# SCH_WGE_Slimevr_rev_2_2_2023-11-07.net
KiCad netlist of a schematic drawn in EasyEDA
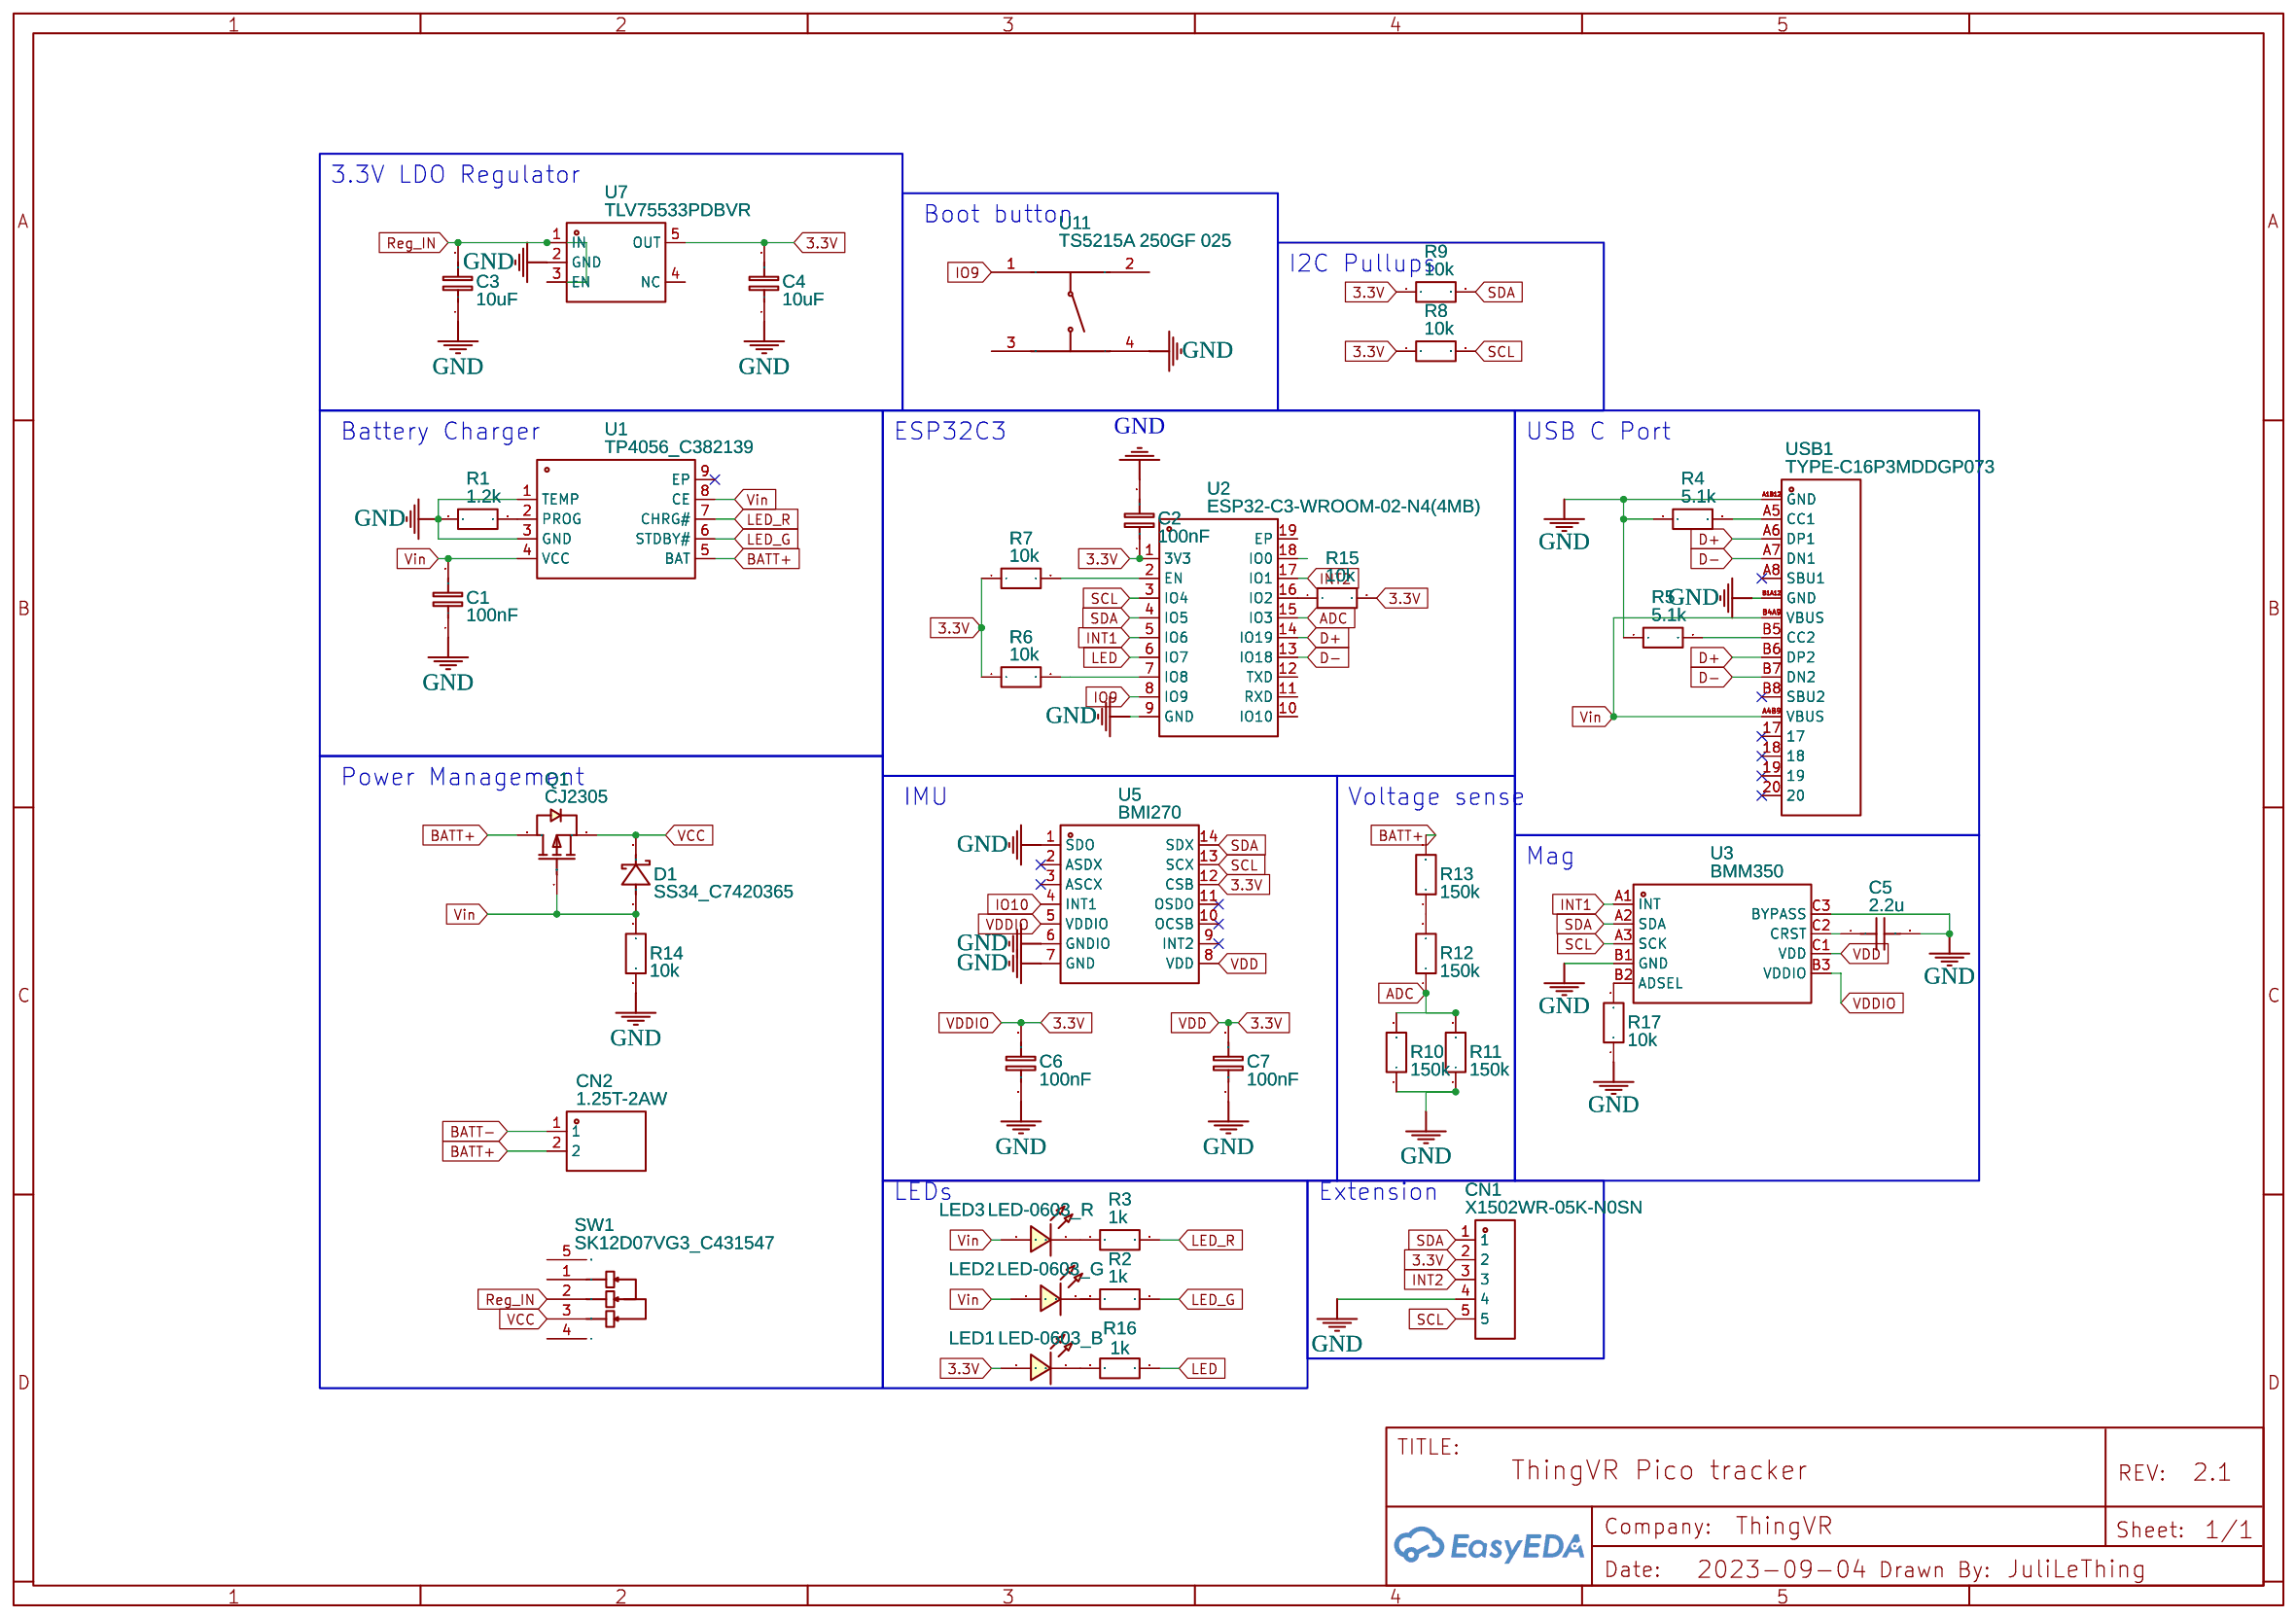
[diagram p0: schematic sheet]

(export (version "E")
  (design (tool "Eeschema 10.0.6"))
  (components
    (comp (ref "C1")
      (value "100nF")
      (fields (field (name "Manufacturer Part") "0603F104Z500CT") (field (name "Manufacturer") "Walsin(华新科)"))
      (libsource (lib "") (part "C_1206_EU"))
    )
    (comp (ref "C2")
      (value "100nF")
      (fields
        (field (name "Manufacturer Part") "CC0805ZRY5V8BB104")
        (field (name "Manufacturer") "YAGEO(国巨)")
      )
      (libsource (lib "") (part "C_0805_EU"))
    )
    (comp (ref "C3")
      (value "10uF")
      (fields
        (field (name "Manufacturer Part") "CC0805KKX5R9BB105")
        (field (name "Manufacturer") "YAGEO(国巨)")
      )
      (libsource (lib "") (part "C_0805_EU_1"))
    )
    (comp (ref "C4")
      (value "10uF")
      (fields
        (field (name "Manufacturer Part") "CC0805KKX5R9BB105")
        (field (name "Manufacturer") "YAGEO(国巨)")
      )
      (libsource (lib "") (part "C_0805_EU_1"))
    )
    (comp (ref "C5") (value "2.2u") (libsource (lib "") (part "C_0603_US")))
    (comp (ref "C6")
      (value "100nF")
      (fields
        (field (name "Manufacturer Part") "CC0805ZRY5V8BB104")
        (field (name "Manufacturer") "YAGEO(国巨)")
      )
      (libsource (lib "") (part "C_0805_EU_2"))
    )
    (comp (ref "C7")
      (value "100nF")
      (fields
        (field (name "Manufacturer Part") "CC0805ZRY5V8BB104")
        (field (name "Manufacturer") "YAGEO(国巨)")
      )
      (libsource (lib "") (part "C_0805_EU_2"))
    )
    (comp (ref "CN1")
      (value "X1502WR-05K-N0SN")
      (fields (field (name "Manufacturer") "XKB Connectivity(中国星坤)"))
      (libsource (lib "") (part "X1502WR-05K-N0SN"))
    )
    (comp (ref "CN2")
      (value "1.25T-2AW")
      (fields (field (name "Manufacturer") "BOOMELE"))
      (libsource (lib "") (part "1.25T-2AW"))
    )
    (comp (ref "D1")
      (value "SS34_C7420365")
      (fields (field (name "Manufacturer Part") "SS34") (field (name "Manufacturer") "宏迦橙"))
      (libsource (lib "") (part "SS34_C7420365"))
    )
    (comp (ref "LED1")
      (value "LED-0603_B")
      (fields
        (field (name "Manufacturer Part") "19-217/BHC-ZL1M2RY/3T")
        (field (name "Manufacturer") "EVERLIGHT(台湾亿光)")
      )
      (libsource (lib "") (part "LED-0603_B"))
    )
    (comp (ref "LED2")
      (value "LED-0603_G")
      (fields (field (name "Manufacturer Part") "NCD0805G1") (field (name "Manufacturer") "国星光电"))
      (libsource (lib "") (part "LED-0805_G"))
    )
    (comp (ref "LED3")
      (value "LED-0603_R")
      (fields
        (field (name "Manufacturer Part") "17-21SURC/S530-A3/TR8")
        (field (name "Manufacturer") "EVERLIGHT(台湾亿光)")
      )
      (libsource (lib "") (part "LED-0805_R"))
    )
    (comp (ref "Q1")
      (value "CJ2305")
      (fields (field (name "Manufacturer") "CJ(江苏长电/长晶)"))
      (libsource (lib "") (part "CJ2305"))
    )
    (comp (ref "R1")
      (value "1.2k")
      (fields (field (name "Manufacturer Part") "RMC08051.2K1%N") (field (name "Manufacturer") "Tyohm(幸亚电阻)"))
      (libsource (lib "") (part "R_1206_EU"))
    )
    (comp (ref "R2")
      (value "1k")
      (fields
        (field (name "Manufacturer Part") "QR0805F1K00P05Z")
        (field (name "Manufacturer") "EVER OHMS(天二科技)")
      )
      (libsource (lib "") (part "R_0805_EU_2"))
    )
    (comp (ref "R3")
      (value "1k")
      (fields
        (field (name "Manufacturer Part") "QR0805F1K00P05Z")
        (field (name "Manufacturer") "EVER OHMS(天二科技)")
      )
      (libsource (lib "") (part "R_0805_EU_1"))
    )
    (comp (ref "R4")
      (value "5.1k")
      (fields (field (name "Manufacturer Part") "RMC08055.1K5%N") (field (name "Manufacturer") "Tyohm(幸亚电阻)"))
      (libsource (lib "") (part "R_0805_EU_1"))
    )
    (comp (ref "R5")
      (value "5.1k")
      (fields (field (name "Manufacturer Part") "RMC08055.1K5%N") (field (name "Manufacturer") "Tyohm(幸亚电阻)"))
      (libsource (lib "") (part "R_0805_EU_1"))
    )
    (comp (ref "R6")
      (value "10k")
      (fields (field (name "Manufacturer Part") "AC0805JR-0710KL") (field (name "Manufacturer") "YAGEO(国巨)"))
      (libsource (lib "") (part "R_0805_EU_1"))
    )
    (comp (ref "R7")
      (value "10k")
      (fields (field (name "Manufacturer Part") "AC0805JR-0710KL") (field (name "Manufacturer") "YAGEO(国巨)"))
      (libsource (lib "") (part "R_0805_EU_1"))
    )
    (comp (ref "R8")
      (value "10k")
      (fields (field (name "Manufacturer Part") "AC0805JR-0710KL") (field (name "Manufacturer") "YAGEO(国巨)"))
      (libsource (lib "") (part "R_0805_EU_1"))
    )
    (comp (ref "R9")
      (value "10k")
      (fields (field (name "Manufacturer Part") "AC0805JR-0710KL") (field (name "Manufacturer") "YAGEO(国巨)"))
      (libsource (lib "") (part "R_0805_EU_1"))
    )
    (comp (ref "R10")
      (value "150k")
      (fields (field (name "Manufacturer Part") "RC0805JR-07300KL") (field (name "Manufacturer") "YAGEO(国巨)"))
      (libsource (lib "") (part "R_0805_EU"))
    )
    (comp (ref "R11")
      (value "150k")
      (fields (field (name "Manufacturer Part") "RC0805JR-07300KL") (field (name "Manufacturer") "YAGEO(国巨)"))
      (libsource (lib "") (part "R_0805_EU"))
    )
    (comp (ref "R12")
      (value "150k")
      (fields (field (name "Manufacturer Part") "RC0805JR-07300KL") (field (name "Manufacturer") "YAGEO(国巨)"))
      (libsource (lib "") (part "R_0805_EU"))
    )
    (comp (ref "R13")
      (value "150k")
      (fields (field (name "Manufacturer Part") "RC0805JR-07300KL") (field (name "Manufacturer") "YAGEO(国巨)"))
      (libsource (lib "") (part "R_0805_EU"))
    )
    (comp (ref "R14")
      (value "10k")
      (fields (field (name "Manufacturer Part") "AC0805JR-0710KL") (field (name "Manufacturer") "YAGEO(国巨)"))
      (libsource (lib "") (part "R_0805_EU"))
    )
    (comp (ref "R15")
      (value "10k")
      (fields (field (name "Manufacturer Part") "AC0805JR-0710KL") (field (name "Manufacturer") "YAGEO(国巨)"))
      (libsource (lib "") (part "R_0805_EU_1"))
    )
    (comp (ref "R16")
      (value "1k")
      (fields (field (name "Manufacturer Part") "SCR0603J1K") (field (name "Manufacturer") "VO(翔胜)"))
      (libsource (lib "") (part "R_0603_EU"))
    )
    (comp (ref "R17") (value "10k") (libsource (lib "") (part "R_0805_EU")))
    (comp (ref "SW1")
      (value "SK12D07VG3_C431547")
      (fields (field (name "Manufacturer Part") "SK12D07VG3") (field (name "Manufacturer") "SHOU HAN"))
      (libsource (lib "") (part "SK12D07VG3_C431547"))
    )
    (comp (ref "U1")
      (value "TP4056_C382139")
      (fields (field (name "Manufacturer Part") "TP4056") (field (name "Manufacturer") "TPOWER(天源)"))
      (libsource (lib "") (part "TP4056_C382139"))
    )
    (comp (ref "U2")
      (value "ESP32-C3-WROOM-02-N4(4MB)")
      (fields
        (field (name "Manufacturer Part") "ESP32-C3-WROOM-02-N4")
        (field (name "Manufacturer") "ESPRESSIF(乐鑫)")
      )
      (libsource (lib "") (part "ESP32-C3-WROOM-02-N4(4MB)"))
    )
    (comp (ref "U3")
      (value "BMM350")
      (fields (field (name "Manufacturer") "Bosch(博世)"))
      (libsource (lib "") (part "BMM350"))
    )
    (comp (ref "U5")
      (value "BMI270")
      (fields (field (name "Manufacturer") "Bosch(博世)"))
      (libsource (lib "") (part "BMI270"))
    )
    (comp (ref "U7")
      (value "TLV75533PDBVR")
      (fields (field (name "Manufacturer") "TI(德州仪器)"))
      (libsource (lib "") (part "TLV75533PDBVR"))
    )
    (comp (ref "U11")
      (value "TS5215A 250GF 025")
      (fields
        (field (name "Manufacturer Part") "TS5215A 250gf 025")
        (field (name "Manufacturer") "SHOU HAN(首韩)")
      )
      (libsource (lib "") (part "TS5215A 250GF 025"))
    )
    (comp (ref "USB1")
      (value "TYPE-C16P3MDDGP073")
      (fields (field (name "Manufacturer") "SHOU HAN(首韩)"))
      (libsource (lib "") (part "TYPE-C16P3MDDGP073"))
    )
  )
  (nets
    (net (code "1") (name "3.3V") (class "Default")
      (node (ref "C2") (pin "1") (pinfunction "1_1") (pintype "unspecified"))
      (node (ref "C4") (pin "2") (pinfunction "2_2") (pintype "unspecified"))
      (node (ref "C6") (pin "2") (pinfunction "2_2") (pintype "unspecified"))
      (node (ref "C7") (pin "2") (pinfunction "2_2") (pintype "unspecified"))
      (node (ref "CN1") (pin "2") (pinfunction "2_2") (pintype "unspecified"))
      (node (ref "LED1") (pin "1") (pinfunction "1_1") (pintype "unspecified"))
      (node (ref "R15") (pin "2") (pinfunction "2_2") (pintype "unspecified"))
      (node (ref "R6") (pin "1") (pinfunction "1_1") (pintype "unspecified"))
      (node (ref "R7") (pin "1") (pinfunction "1_1") (pintype "unspecified"))
      (node (ref "R8") (pin "1") (pinfunction "1_1") (pintype "unspecified"))
      (node (ref "R9") (pin "1") (pinfunction "1_1") (pintype "unspecified"))
      (node (ref "U2") (pin "1") (pinfunction "3V3_1") (pintype "unspecified"))
      (node (ref "U3") (pin "B3") (pinfunction "VDDIO_B3") (pintype "unspecified"))
      (node (ref "U3") (pin "C1") (pinfunction "VDD_C1") (pintype "unspecified"))
      (node (ref "U5") (pin "12") (pinfunction "CSB_12") (pintype "unspecified"))
      (node (ref "U5") (pin "5") (pinfunction "VDDIO_5") (pintype "unspecified"))
      (node (ref "U5") (pin "8") (pinfunction "VDD_8") (pintype "unspecified"))
      (node (ref "U7") (pin "5") (pinfunction "OUT_5") (pintype "unspecified"))
    )
    (net (code "2") (name "ADC") (class "Default")
      (node (ref "R10") (pin "2") (pinfunction "2_2") (pintype "unspecified"))
      (node (ref "R11") (pin "2") (pinfunction "2_2") (pintype "unspecified"))
      (node (ref "R12") (pin "1") (pinfunction "1_1") (pintype "unspecified"))
      (node (ref "U2") (pin "15") (pinfunction "IO3_15") (pintype "unspecified"))
    )
    (net (code "3") (name "BATT+") (class "Default")
      (node (ref "CN2") (pin "2") (pinfunction "2_2") (pintype "unspecified"))
      (node (ref "Q1") (pin "3") (pinfunction "D_3") (pintype "unspecified"))
      (node (ref "R13") (pin "2") (pinfunction "2_2") (pintype "unspecified"))
      (node (ref "U1") (pin "5") (pinfunction "BAT_5") (pintype "unspecified"))
    )
    (net (code "4") (name "BATT-") (class "Default")
      (node (ref "CN2") (pin "1") (pinfunction "1_1") (pintype "unspecified"))
    )
    (net (code "5") (name "D+") (class "Default")
      (node (ref "U2") (pin "14") (pinfunction "IO19_14") (pintype "unspecified"))
      (node (ref "USB1") (pin "A6") (pinfunction "DP1_A6") (pintype "unspecified"))
      (node (ref "USB1") (pin "B6") (pinfunction "DP2_B6") (pintype "unspecified"))
    )
    (net (code "6") (name "D-") (class "Default")
      (node (ref "U2") (pin "13") (pinfunction "IO18_13") (pintype "unspecified"))
      (node (ref "USB1") (pin "A7") (pinfunction "DN1_A7") (pintype "unspecified"))
      (node (ref "USB1") (pin "B7") (pinfunction "DN2_B7") (pintype "unspecified"))
    )
    (net (code "7") (name "GND") (class "Default")
      (node (ref "C1") (pin "1") (pinfunction "1_1") (pintype "unspecified"))
      (node (ref "C2") (pin "2") (pinfunction "2_2") (pintype "unspecified"))
      (node (ref "C3") (pin "1") (pinfunction "1_1") (pintype "unspecified"))
      (node (ref "C4") (pin "1") (pinfunction "1_1") (pintype "unspecified"))
      (node (ref "C5") (pin "2") (pinfunction "2_2") (pintype "unspecified"))
      (node (ref "C6") (pin "1") (pinfunction "1_1") (pintype "unspecified"))
      (node (ref "C7") (pin "1") (pinfunction "1_1") (pintype "unspecified"))
      (node (ref "CN1") (pin "4") (pinfunction "4_4") (pintype "unspecified"))
      (node (ref "R1") (pin "1") (pinfunction "1_1") (pintype "unspecified"))
      (node (ref "R10") (pin "1") (pinfunction "1_1") (pintype "unspecified"))
      (node (ref "R11") (pin "1") (pinfunction "1_1") (pintype "unspecified"))
      (node (ref "R14") (pin "1") (pinfunction "1_1") (pintype "unspecified"))
      (node (ref "R17") (pin "1") (pinfunction "1_1") (pintype "unspecified"))
      (node (ref "R4") (pin "1") (pinfunction "1_1") (pintype "unspecified"))
      (node (ref "R5") (pin "1") (pinfunction "1_1") (pintype "unspecified"))
      (node (ref "U1") (pin "1") (pinfunction "TEMP_1") (pintype "unspecified"))
      (node (ref "U1") (pin "3") (pinfunction "GND_3") (pintype "unspecified"))
      (node (ref "U11") (pin "4") (pinfunction "4_4") (pintype "unspecified"))
      (node (ref "U2") (pin "9") (pinfunction "GND_9") (pintype "unspecified"))
      (node (ref "U3") (pin "B1") (pinfunction "GND_B1") (pintype "unspecified"))
      (node (ref "U3") (pin "C3") (pinfunction "BYPASS_C3") (pintype "unspecified"))
      (node (ref "U5") (pin "1") (pinfunction "SDO_1") (pintype "unspecified"))
      (node (ref "U5") (pin "6") (pinfunction "GNDIO_6") (pintype "unspecified"))
      (node (ref "U5") (pin "7") (pinfunction "GND_7") (pintype "unspecified"))
      (node (ref "U7") (pin "2") (pinfunction "GND_2") (pintype "unspecified"))
      (node (ref "USB1") (pin "A1B12") (pinfunction "GND_A1B12") (pintype "unspecified"))
      (node (ref "USB1") (pin "B1A12") (pinfunction "GND_B1A12") (pintype "unspecified"))
    )
    (net (code "8") (name "INT1") (class "Default")
      (node (ref "U2") (pin "5") (pinfunction "IO6_5") (pintype "unspecified"))
      (node (ref "U3") (pin "A1") (pinfunction "INT_A1") (pintype "unspecified"))
    )
    (net (code "9") (name "INT2") (class "Default")
      (node (ref "CN1") (pin "3") (pinfunction "3_3") (pintype "unspecified"))
      (node (ref "U2") (pin "17") (pinfunction "IO1_17") (pintype "unspecified"))
    )
    (net (code "10") (name "IO9") (class "Default")
      (node (ref "U11") (pin "1") (pinfunction "1_1") (pintype "unspecified"))
      (node (ref "U2") (pin "8") (pinfunction "IO9_8") (pintype "unspecified"))
    )
    (net (code "11") (name "IO10") (class "Default")
      (node (ref "U5") (pin "4") (pinfunction "INT1_4") (pintype "unspecified"))
    )
    (net (code "12") (name "LED") (class "Default")
      (node (ref "R16") (pin "1") (pinfunction "1_1") (pintype "unspecified"))
      (node (ref "U2") (pin "6") (pinfunction "IO7_6") (pintype "unspecified"))
    )
    (net (code "13") (name "LED_G") (class "Default")
      (node (ref "R2") (pin "1") (pinfunction "1_1") (pintype "unspecified"))
      (node (ref "U1") (pin "6") (pinfunction "STDBY#_6") (pintype "unspecified"))
    )
    (net (code "14") (name "LED_R") (class "Default")
      (node (ref "R3") (pin "2") (pinfunction "2_2") (pintype "unspecified"))
      (node (ref "U1") (pin "7") (pinfunction "CHRG#_7") (pintype "unspecified"))
    )
    (net (code "15") (name "Net-(LED1-Pad2)") (class "Default")
      (node (ref "LED1") (pin "2") (pinfunction "2_2") (pintype "unspecified"))
      (node (ref "R16") (pin "2") (pinfunction "2_2") (pintype "unspecified"))
    )
    (net (code "16") (name "Net-(LED2-Pad2)") (class "Default")
      (node (ref "LED2") (pin "2") (pinfunction "2_2") (pintype "unspecified"))
      (node (ref "R2") (pin "2") (pinfunction "2_2") (pintype "unspecified"))
    )
    (net (code "17") (name "Net-(LED3-Pad2)") (class "Default")
      (node (ref "LED3") (pin "2") (pinfunction "2_2") (pintype "unspecified"))
      (node (ref "R3") (pin "1") (pinfunction "1_1") (pintype "unspecified"))
    )
    (net (code "18") (name "Net-(R12-Pad2)") (class "Default")
      (node (ref "R12") (pin "2") (pinfunction "2_2") (pintype "unspecified"))
      (node (ref "R13") (pin "1") (pinfunction "1_1") (pintype "unspecified"))
    )
    (net (code "19") (name "Net-(U1-PROG)") (class "Default")
      (node (ref "R1") (pin "2") (pinfunction "2_2") (pintype "unspecified"))
      (node (ref "U1") (pin "2") (pinfunction "PROG_2") (pintype "unspecified"))
    )
    (net (code "20") (name "Net-(U2-EN)") (class "Default")
      (node (ref "R7") (pin "2") (pinfunction "2_2") (pintype "unspecified"))
      (node (ref "U2") (pin "2") (pinfunction "EN_2") (pintype "unspecified"))
    )
    (net (code "21") (name "Net-(U2-IO2)") (class "Default")
      (node (ref "R15") (pin "1") (pinfunction "1_1") (pintype "unspecified"))
      (node (ref "U2") (pin "16") (pinfunction "IO2_16") (pintype "unspecified"))
    )
    (net (code "22") (name "Net-(U2-IO8)") (class "Default")
      (node (ref "R6") (pin "2") (pinfunction "2_2") (pintype "unspecified"))
      (node (ref "U2") (pin "7") (pinfunction "IO8_7") (pintype "unspecified"))
    )
    (net (code "23") (name "Net-(U3-ADSEL)") (class "Default")
      (node (ref "R17") (pin "2") (pinfunction "2_2") (pintype "unspecified"))
      (node (ref "U3") (pin "B2") (pinfunction "ADSEL_B2") (pintype "unspecified"))
    )
    (net (code "24") (name "Net-(U3-CRST)") (class "Default")
      (node (ref "C5") (pin "1") (pinfunction "1_1") (pintype "unspecified"))
      (node (ref "U3") (pin "C2") (pinfunction "CRST_C2") (pintype "unspecified"))
    )
    (net (code "25") (name "Net-(USB1-CC1)") (class "Default")
      (node (ref "R4") (pin "2") (pinfunction "2_2") (pintype "unspecified"))
      (node (ref "USB1") (pin "A5") (pinfunction "CC1_A5") (pintype "unspecified"))
    )
    (net (code "26") (name "Net-(USB1-CC2)") (class "Default")
      (node (ref "R5") (pin "2") (pinfunction "2_2") (pintype "unspecified"))
      (node (ref "USB1") (pin "B5") (pinfunction "CC2_B5") (pintype "unspecified"))
    )
    (net (code "27") (name "Reg_IN") (class "Default")
      (node (ref "C3") (pin "2") (pinfunction "2_2") (pintype "unspecified"))
      (node (ref "SW1") (pin "2") (pinfunction "2_2") (pintype "unspecified"))
      (node (ref "U7") (pin "1") (pinfunction "IN_1") (pintype "unspecified"))
      (node (ref "U7") (pin "3") (pinfunction "EN_3") (pintype "unspecified"))
    )
    (net (code "28") (name "SCL") (class "Default")
      (node (ref "CN1") (pin "5") (pinfunction "5_5") (pintype "unspecified"))
      (node (ref "R8") (pin "2") (pinfunction "2_2") (pintype "unspecified"))
      (node (ref "U2") (pin "3") (pinfunction "IO4_3") (pintype "unspecified"))
      (node (ref "U3") (pin "A3") (pinfunction "SCK_A3") (pintype "unspecified"))
      (node (ref "U5") (pin "13") (pinfunction "SCX_13") (pintype "unspecified"))
    )
    (net (code "29") (name "SDA") (class "Default")
      (node (ref "CN1") (pin "1") (pinfunction "1_1") (pintype "unspecified"))
      (node (ref "R9") (pin "2") (pinfunction "2_2") (pintype "unspecified"))
      (node (ref "U2") (pin "4") (pinfunction "IO5_4") (pintype "unspecified"))
      (node (ref "U3") (pin "A2") (pinfunction "SDA_A2") (pintype "unspecified"))
      (node (ref "U5") (pin "14") (pinfunction "SDX_14") (pintype "unspecified"))
    )
    (net (code "30") (name "VCC") (class "Default")
      (node (ref "D1") (pin "2") (pinfunction "K_2") (pintype "unspecified"))
      (node (ref "Q1") (pin "2") (pinfunction "S_2") (pintype "unspecified"))
      (node (ref "SW1") (pin "3") (pinfunction "3_3") (pintype "unspecified"))
    )
    (net (code "31") (name "Vin") (class "Default")
      (node (ref "C1") (pin "2") (pinfunction "2_2") (pintype "unspecified"))
      (node (ref "D1") (pin "1") (pinfunction "A_1") (pintype "unspecified"))
      (node (ref "LED2") (pin "1") (pinfunction "1_1") (pintype "unspecified"))
      (node (ref "LED3") (pin "1") (pinfunction "1_1") (pintype "unspecified"))
      (node (ref "Q1") (pin "1") (pinfunction "G_1") (pintype "unspecified"))
      (node (ref "R14") (pin "2") (pinfunction "2_2") (pintype "unspecified"))
      (node (ref "U1") (pin "4") (pinfunction "VCC_4") (pintype "unspecified"))
      (node (ref "U1") (pin "8") (pinfunction "CE_8") (pintype "unspecified"))
      (node (ref "USB1") (pin "A4B9") (pinfunction "VBUS_A4B9") (pintype "unspecified"))
      (node (ref "USB1") (pin "B4A9") (pinfunction "VBUS_B4A9") (pintype "unspecified"))
    )
    (net (code "32") (name "unconnected-(SW1-Pad1)") (class "Default")
      (node (ref "SW1") (pin "1") (pinfunction "1_1") (pintype "unspecified"))
    )
    (net (code "33") (name "unconnected-(SW1-Pad4)") (class "Default")
      (node (ref "SW1") (pin "4") (pinfunction "4_4") (pintype "unspecified"))
    )
    (net (code "34") (name "unconnected-(SW1-Pad5)") (class "Default")
      (node (ref "SW1") (pin "5") (pinfunction "5_5") (pintype "unspecified"))
    )
    (net (code "35") (name "unconnected-(U1-EP-Pad9)") (class "Default")
      (node (ref "U1") (pin "9") (pinfunction "EP_9") (pintype "unspecified+no_connect"))
    )
    (net (code "36") (name "unconnected-(U2-EP-Pad19)") (class "Default")
      (node (ref "U2") (pin "19") (pinfunction "EP_19") (pintype "unspecified"))
    )
    (net (code "37") (name "unconnected-(U2-IO0-Pad18)") (class "Default")
      (node (ref "U2") (pin "18") (pinfunction "IO0_18") (pintype "unspecified"))
    )
    (net (code "38") (name "unconnected-(U2-IO10-Pad10)") (class "Default")
      (node (ref "U2") (pin "10") (pinfunction "IO10_10") (pintype "unspecified"))
    )
    (net (code "39") (name "unconnected-(U2-RXD-Pad11)") (class "Default")
      (node (ref "U2") (pin "11") (pinfunction "RXD_11") (pintype "unspecified"))
    )
    (net (code "40") (name "unconnected-(U2-TXD-Pad12)") (class "Default")
      (node (ref "U2") (pin "12") (pinfunction "TXD_12") (pintype "unspecified"))
    )
    (net (code "41") (name "unconnected-(U5-ASCX-Pad3)") (class "Default")
      (node (ref "U5") (pin "3") (pinfunction "ASCX_3") (pintype "unspecified+no_connect"))
    )
    (net (code "42") (name "unconnected-(U5-ASDX-Pad2)") (class "Default")
      (node (ref "U5") (pin "2") (pinfunction "ASDX_2") (pintype "unspecified+no_connect"))
    )
    (net (code "43") (name "unconnected-(U5-INT2-Pad9)") (class "Default")
      (node (ref "U5") (pin "9") (pinfunction "INT2_9") (pintype "unspecified+no_connect"))
    )
    (net (code "44") (name "unconnected-(U5-OCSB-Pad10)") (class "Default")
      (node (ref "U5") (pin "10") (pinfunction "OCSB_10") (pintype "unspecified+no_connect"))
    )
    (net (code "45") (name "unconnected-(U5-OSDO-Pad11)") (class "Default")
      (node (ref "U5") (pin "11") (pinfunction "OSDO_11") (pintype "unspecified+no_connect"))
    )
    (net (code "46") (name "unconnected-(U7-NC-Pad4)") (class "Default")
      (node (ref "U7") (pin "4") (pinfunction "NC_4") (pintype "unspecified"))
    )
    (net (code "47") (name "unconnected-(U11-Pad2)") (class "Default")
      (node (ref "U11") (pin "2") (pinfunction "2_2") (pintype "unspecified"))
    )
    (net (code "48") (name "unconnected-(U11-Pad3)") (class "Default")
      (node (ref "U11") (pin "3") (pinfunction "3_3") (pintype "unspecified"))
    )
    (net (code "49") (name "unconnected-(USB1-Pad17)") (class "Default")
      (node (ref "USB1") (pin "17") (pinfunction "17_17") (pintype "unspecified+no_connect"))
    )
    (net (code "50") (name "unconnected-(USB1-Pad18)") (class "Default")
      (node (ref "USB1") (pin "18") (pinfunction "18_18") (pintype "unspecified+no_connect"))
    )
    (net (code "51") (name "unconnected-(USB1-Pad19)") (class "Default")
      (node (ref "USB1") (pin "19") (pinfunction "19_19") (pintype "unspecified+no_connect"))
    )
    (net (code "52") (name "unconnected-(USB1-Pad20)") (class "Default")
      (node (ref "USB1") (pin "20") (pinfunction "20_20") (pintype "unspecified+no_connect"))
    )
    (net (code "53") (name "unconnected-(USB1-SBU1-PadA8)") (class "Default")
      (node (ref "USB1") (pin "A8") (pinfunction "SBU1_A8") (pintype "unspecified+no_connect"))
    )
    (net (code "54") (name "unconnected-(USB1-SBU2-PadB8)") (class "Default")
      (node (ref "USB1") (pin "B8") (pinfunction "SBU2_B8") (pintype "unspecified+no_connect"))
    )
  )
)
